# STM32H750-MotherBoard2.net
KiCad netlist of a schematic drawn in Altium Designer
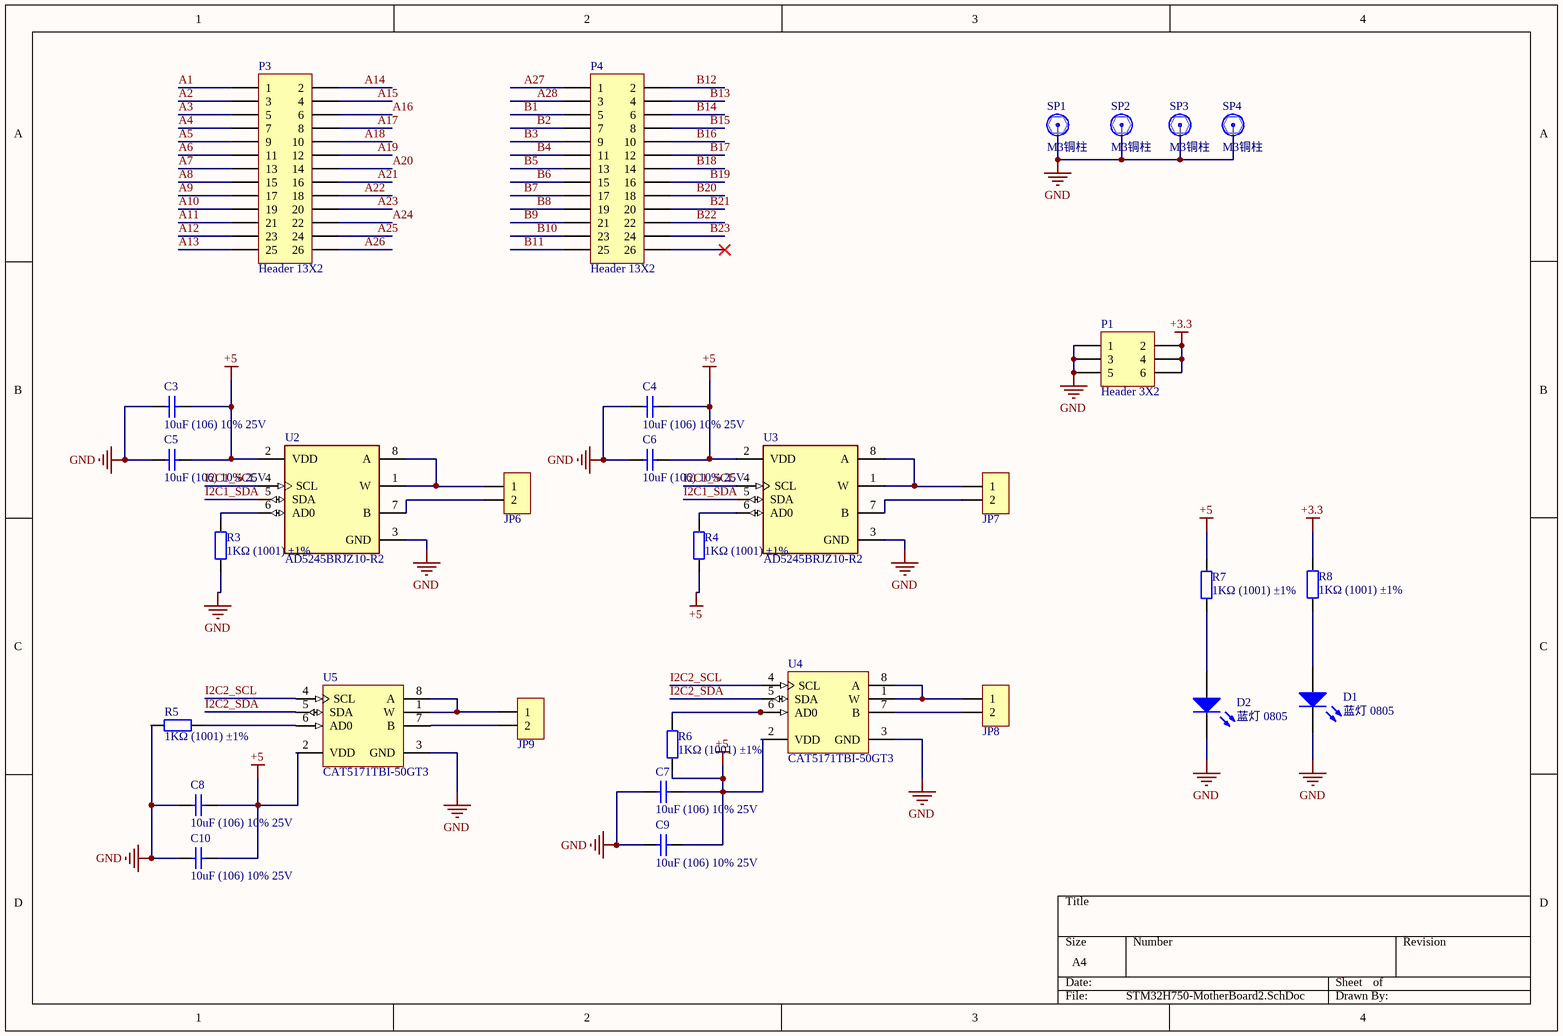
[diagram p0: STM32H750-MotherBoard2.SchDoc]

(export (version "E")
  (design (tool "Eeschema 10.0.6"))
  (components
    (comp (ref "C3")
      (value "10uF (106) 10% 25V")
      (footprint "0805_C")
      (description "贴片电容")
      (libsource (lib "JLC") (part "0805 10uF (106) 10% 25V"))
    )
    (comp (ref "C4")
      (value "10uF (106) 10% 25V")
      (footprint "0805_C")
      (description "贴片电容")
      (libsource (lib "JLC") (part "0805 10uF (106) 10% 25V"))
    )
    (comp (ref "C5")
      (value "10uF (106) 10% 25V")
      (footprint "0805_C")
      (description "贴片电容")
      (libsource (lib "JLC") (part "0805 10uF (106) 10% 25V"))
    )
    (comp (ref "C6")
      (value "10uF (106) 10% 25V")
      (footprint "0805_C")
      (description "贴片电容")
      (libsource (lib "JLC") (part "0805 10uF (106) 10% 25V"))
    )
    (comp (ref "C7")
      (value "10uF (106) 10% 25V")
      (footprint "0805_C")
      (description "贴片电容")
      (libsource (lib "JLC") (part "0805 10uF (106) 10% 25V"))
    )
    (comp (ref "C8")
      (value "10uF (106) 10% 25V")
      (footprint "0805_C")
      (description "贴片电容")
      (libsource (lib "JLC") (part "0805 10uF (106) 10% 25V"))
    )
    (comp (ref "C9")
      (value "10uF (106) 10% 25V")
      (footprint "0805_C")
      (description "贴片电容")
      (libsource (lib "JLC") (part "0805 10uF (106) 10% 25V"))
    )
    (comp (ref "C10")
      (value "10uF (106) 10% 25V")
      (footprint "0805_C")
      (description "贴片电容")
      (libsource (lib "JLC") (part "0805 10uF (106) 10% 25V"))
    )
    (comp (ref "D1")
      (value "蓝灯 0805")
      (footprint "0805_LED_S1")
      (description "发光二极管")
      (libsource (lib "JLC") (part "0805 蓝灯"))
    )
    (comp (ref "D2")
      (value "蓝灯 0805")
      (footprint "0805_LED_S1")
      (description "发光二极管")
      (libsource (lib "JLC") (part "0805 蓝灯"))
    )
    (comp (ref "JP6")
      (value "HDR-1X2")
      (footprint "XH2.54-LI-2P")
      (description "2P接插件")
      (libsource (lib "XH2.54") (part "Header 2"))
    )
    (comp (ref "JP7")
      (value "HDR-1X2")
      (footprint "XH2.54-LI-2P")
      (description "2P接插件")
      (libsource (lib "XH2.54") (part "Header 2"))
    )
    (comp (ref "JP8")
      (value "HDR-1X2")
      (footprint "XH2.54-LI-2P")
      (description "2P接插件")
      (libsource (lib "XH2.54") (part "Header 2"))
    )
    (comp (ref "JP9")
      (value "HDR-1X2")
      (footprint "XH2.54-LI-2P")
      (description "2P接插件")
      (libsource (lib "XH2.54") (part "Header 2"))
    )
    (comp (ref "P1")
      (value "Header 3X2")
      (footprint "HDR2X3")
      (description "Header, 3-Pin, Dual row")
      (fields (field (name "PUBLISHER") "Altium Limited"))
      (libsource (lib "Miscellaneous Connectors") (part "Header 3X2"))
    )
    (comp (ref "P3")
      (value "Header 13X2")
      (footprint "HDR2X13")
      (description "Header, 13-Pin, Dual row")
      (fields (field (name "PUBLISHER") "Altium Limited"))
      (libsource (lib "Miscellaneous Connectors") (part "Header 13X2"))
    )
    (comp (ref "P4")
      (value "Header 13X2")
      (footprint "HDR2X13")
      (description "Header, 13-Pin, Dual row")
      (fields (field (name "PUBLISHER") "Altium Limited"))
      (libsource (lib "Miscellaneous Connectors") (part "Header 13X2"))
    )
    (comp (ref "R3")
      (value "1KΩ (1001) ±1%")
      (footprint "0805_R")
      (description "贴片电阻")
      (libsource (lib "JLC") (part "0805 1KΩ (1001) 1%"))
    )
    (comp (ref "R4")
      (value "1KΩ (1001) ±1%")
      (footprint "0805_R")
      (description "贴片电阻")
      (libsource (lib "JLC") (part "0805 1KΩ (1001) 1%"))
    )
    (comp (ref "R5")
      (value "1KΩ (1001) ±1%")
      (footprint "0805_R")
      (description "贴片电阻")
      (libsource (lib "") (part "0805 1KΩ (1001) 1%_1"))
    )
    (comp (ref "R6")
      (value "1KΩ (1001) ±1%")
      (footprint "0805_R")
      (description "贴片电阻")
      (libsource (lib "JLC") (part "0805 1KΩ (1001) 1%"))
    )
    (comp (ref "R7")
      (value "1KΩ (1001) ±1%")
      (footprint "0805_R")
      (description "贴片电阻")
      (libsource (lib "JLC") (part "0805 1KΩ (1001) 1%"))
    )
    (comp (ref "R8")
      (value "1KΩ (1001) ±1%")
      (footprint "0805_R")
      (description "贴片电阻")
      (libsource (lib "JLC") (part "0805 1KΩ (1001) 1%"))
    )
    (comp (ref "SP1")
      (value "M3铜柱")
      (footprint "M3x4_L")
      (description "铜柱")
      (libsource (lib "铜柱-测试点-电池座-蜂鸣器") (part "铜柱小焊盘"))
    )
    (comp (ref "SP2")
      (value "M3铜柱")
      (footprint "M3x4_L")
      (description "铜柱")
      (libsource (lib "铜柱-测试点-电池座-蜂鸣器") (part "铜柱小焊盘"))
    )
    (comp (ref "SP3")
      (value "M3铜柱")
      (footprint "M3x4_L")
      (description "铜柱")
      (libsource (lib "铜柱-测试点-电池座-蜂鸣器") (part "铜柱小焊盘"))
    )
    (comp (ref "SP4")
      (value "M3铜柱")
      (footprint "M3x4_L")
      (description "铜柱")
      (libsource (lib "铜柱-测试点-电池座-蜂鸣器") (part "铜柱小焊盘"))
    )
    (comp (ref "U2")
      (value "AD5245BRJZ10-R2")
      (footprint "FP-RJ-8-IPC_C")
      (description "IC DGT POT 10KOHM 256TAP SOT23-8")
      (fields (field (name "TOLERANCE") "30%") (field (name "MANUFACTURER") "Analog Devices"))
      (libsource (lib "Altium Content Vault") (part "8d408c839f24318d0976f3536df8182"))
    )
    (comp (ref "U3")
      (value "AD5245BRJZ10-R2")
      (footprint "FP-RJ-8-IPC_C")
      (description "IC DGT POT 10KOHM 256TAP SOT23-8")
      (fields (field (name "TOLERANCE") "30%") (field (name "MANUFACTURER") "Analog Devices"))
      (libsource (lib "Altium Content Vault") (part "8d408c839f24318d0976f3536df8182"))
    )
    (comp (ref "U4")
      (value "CAT5171TBI-50GT3")
      (footprint "ONSC-SOT23-8-527AK-01_N")
      (fields (field (name "MANUFACTURER") "On Semiconductor"))
      (libsource (lib "Altium Content Vault") (part "ONSC-CAT5171-SOT23-8-527AK-01"))
    )
    (comp (ref "U5")
      (value "CAT5171TBI-50GT3")
      (footprint "ONSC-SOT23-8-527AK-01_N")
      (fields (field (name "MANUFACTURER") "On Semiconductor"))
      (libsource (lib "Altium Content Vault") (part "ONSC-CAT5171-SOT23-8-527AK-01"))
    )
  )
  (nets
    (net (code "1") (name "+3.3") (class "Default")
      (node (ref "P1") (pin "2") (pinfunction "2_2") (pintype "passive"))
      (node (ref "P1") (pin "4") (pinfunction "4_4") (pintype "passive"))
      (node (ref "P1") (pin "6") (pinfunction "6_6") (pintype "passive"))
      (node (ref "R8") (pin "2") (pinfunction "2_2") (pintype "passive"))
    )
    (net (code "2") (name "+5") (class "Default")
      (node (ref "C10") (pin "2") (pinfunction "2_2") (pintype "passive"))
      (node (ref "C3") (pin "2") (pinfunction "2_2") (pintype "passive"))
      (node (ref "C4") (pin "2") (pinfunction "2_2") (pintype "passive"))
      (node (ref "C5") (pin "2") (pinfunction "2_2") (pintype "passive"))
      (node (ref "C6") (pin "2") (pinfunction "2_2") (pintype "passive"))
      (node (ref "C7") (pin "2") (pinfunction "2_2") (pintype "passive"))
      (node (ref "C8") (pin "2") (pinfunction "2_2") (pintype "passive"))
      (node (ref "C9") (pin "2") (pinfunction "2_2") (pintype "passive"))
      (node (ref "R4") (pin "1") (pinfunction "1_1") (pintype "passive"))
      (node (ref "R6") (pin "1") (pinfunction "1_1") (pintype "passive"))
      (node (ref "R7") (pin "2") (pinfunction "2_2") (pintype "passive"))
      (node (ref "U2") (pin "2") (pinfunction "VDD_2") (pintype "power_in"))
      (node (ref "U3") (pin "2") (pinfunction "VDD_2") (pintype "power_in"))
      (node (ref "U4") (pin "2") (pinfunction "VDD_2") (pintype "power_in"))
      (node (ref "U5") (pin "2") (pinfunction "VDD_2") (pintype "power_in"))
    )
    (net (code "3") (name "/A1") (class "Default")
      (node (ref "P3") (pin "1") (pinfunction "1_1") (pintype "passive"))
    )
    (net (code "4") (name "/A2") (class "Default")
      (node (ref "P3") (pin "3") (pinfunction "3_3") (pintype "passive"))
    )
    (net (code "5") (name "/A3") (class "Default")
      (node (ref "P3") (pin "5") (pinfunction "5_5") (pintype "passive"))
    )
    (net (code "6") (name "/A4") (class "Default")
      (node (ref "P3") (pin "7") (pinfunction "7_7") (pintype "passive"))
    )
    (net (code "7") (name "/A5") (class "Default")
      (node (ref "P3") (pin "9") (pinfunction "9_9") (pintype "passive"))
    )
    (net (code "8") (name "/A6") (class "Default")
      (node (ref "P3") (pin "11") (pinfunction "11_11") (pintype "passive"))
    )
    (net (code "9") (name "/A7") (class "Default")
      (node (ref "P3") (pin "13") (pinfunction "13_13") (pintype "passive"))
    )
    (net (code "10") (name "/A8") (class "Default")
      (node (ref "P3") (pin "15") (pinfunction "15_15") (pintype "passive"))
    )
    (net (code "11") (name "/A9") (class "Default")
      (node (ref "P3") (pin "17") (pinfunction "17_17") (pintype "passive"))
    )
    (net (code "12") (name "/A10") (class "Default")
      (node (ref "P3") (pin "19") (pinfunction "19_19") (pintype "passive"))
    )
    (net (code "13") (name "/A11") (class "Default")
      (node (ref "P3") (pin "21") (pinfunction "21_21") (pintype "passive"))
    )
    (net (code "14") (name "/A12") (class "Default")
      (node (ref "P3") (pin "23") (pinfunction "23_23") (pintype "passive"))
    )
    (net (code "15") (name "/A13") (class "Default")
      (node (ref "P3") (pin "25") (pinfunction "25_25") (pintype "passive"))
    )
    (net (code "16") (name "/A14") (class "Default")
      (node (ref "P3") (pin "2") (pinfunction "2_2") (pintype "passive"))
    )
    (net (code "17") (name "/A15") (class "Default")
      (node (ref "P3") (pin "4") (pinfunction "4_4") (pintype "passive"))
    )
    (net (code "18") (name "/A16") (class "Default")
      (node (ref "P3") (pin "6") (pinfunction "6_6") (pintype "passive"))
    )
    (net (code "19") (name "/A17") (class "Default")
      (node (ref "P3") (pin "8") (pinfunction "8_8") (pintype "passive"))
    )
    (net (code "20") (name "/A18") (class "Default")
      (node (ref "P3") (pin "10") (pinfunction "10_10") (pintype "passive"))
    )
    (net (code "21") (name "/A19") (class "Default")
      (node (ref "P3") (pin "12") (pinfunction "12_12") (pintype "passive"))
    )
    (net (code "22") (name "/A20") (class "Default")
      (node (ref "P3") (pin "14") (pinfunction "14_14") (pintype "passive"))
    )
    (net (code "23") (name "/A21") (class "Default")
      (node (ref "P3") (pin "16") (pinfunction "16_16") (pintype "passive"))
    )
    (net (code "24") (name "/A22") (class "Default")
      (node (ref "P3") (pin "18") (pinfunction "18_18") (pintype "passive"))
    )
    (net (code "25") (name "/A23") (class "Default")
      (node (ref "P3") (pin "20") (pinfunction "20_20") (pintype "passive"))
    )
    (net (code "26") (name "/A24") (class "Default")
      (node (ref "P3") (pin "22") (pinfunction "22_22") (pintype "passive"))
    )
    (net (code "27") (name "/A25") (class "Default")
      (node (ref "P3") (pin "24") (pinfunction "24_24") (pintype "passive"))
    )
    (net (code "28") (name "/A26") (class "Default")
      (node (ref "P3") (pin "26") (pinfunction "26_26") (pintype "passive"))
    )
    (net (code "29") (name "/A27") (class "Default")
      (node (ref "P4") (pin "1") (pinfunction "1_1") (pintype "passive"))
    )
    (net (code "30") (name "/A28") (class "Default")
      (node (ref "P4") (pin "3") (pinfunction "3_3") (pintype "passive"))
    )
    (net (code "31") (name "/B1") (class "Default")
      (node (ref "P4") (pin "5") (pinfunction "5_5") (pintype "passive"))
    )
    (net (code "32") (name "/B2") (class "Default")
      (node (ref "P4") (pin "7") (pinfunction "7_7") (pintype "passive"))
    )
    (net (code "33") (name "/B3") (class "Default")
      (node (ref "P4") (pin "9") (pinfunction "9_9") (pintype "passive"))
    )
    (net (code "34") (name "/B4") (class "Default")
      (node (ref "P4") (pin "11") (pinfunction "11_11") (pintype "passive"))
    )
    (net (code "35") (name "/B5") (class "Default")
      (node (ref "P4") (pin "13") (pinfunction "13_13") (pintype "passive"))
    )
    (net (code "36") (name "/B6") (class "Default")
      (node (ref "P4") (pin "15") (pinfunction "15_15") (pintype "passive"))
    )
    (net (code "37") (name "/B7") (class "Default")
      (node (ref "P4") (pin "17") (pinfunction "17_17") (pintype "passive"))
    )
    (net (code "38") (name "/B8") (class "Default")
      (node (ref "P4") (pin "19") (pinfunction "19_19") (pintype "passive"))
    )
    (net (code "39") (name "/B9") (class "Default")
      (node (ref "P4") (pin "21") (pinfunction "21_21") (pintype "passive"))
    )
    (net (code "40") (name "/B10") (class "Default")
      (node (ref "P4") (pin "23") (pinfunction "23_23") (pintype "passive"))
    )
    (net (code "41") (name "/B11") (class "Default")
      (node (ref "P4") (pin "25") (pinfunction "25_25") (pintype "passive"))
    )
    (net (code "42") (name "/B12") (class "Default")
      (node (ref "P4") (pin "2") (pinfunction "2_2") (pintype "passive"))
    )
    (net (code "43") (name "/B13") (class "Default")
      (node (ref "P4") (pin "4") (pinfunction "4_4") (pintype "passive"))
    )
    (net (code "44") (name "/B14") (class "Default")
      (node (ref "P4") (pin "6") (pinfunction "6_6") (pintype "passive"))
    )
    (net (code "45") (name "/B15") (class "Default")
      (node (ref "P4") (pin "8") (pinfunction "8_8") (pintype "passive"))
    )
    (net (code "46") (name "/B16") (class "Default")
      (node (ref "P4") (pin "10") (pinfunction "10_10") (pintype "passive"))
    )
    (net (code "47") (name "/B17") (class "Default")
      (node (ref "P4") (pin "12") (pinfunction "12_12") (pintype "passive"))
    )
    (net (code "48") (name "/B18") (class "Default")
      (node (ref "P4") (pin "14") (pinfunction "14_14") (pintype "passive"))
    )
    (net (code "49") (name "/B19") (class "Default")
      (node (ref "P4") (pin "16") (pinfunction "16_16") (pintype "passive"))
    )
    (net (code "50") (name "/B20") (class "Default")
      (node (ref "P4") (pin "18") (pinfunction "18_18") (pintype "passive"))
    )
    (net (code "51") (name "/B21") (class "Default")
      (node (ref "P4") (pin "20") (pinfunction "20_20") (pintype "passive"))
    )
    (net (code "52") (name "/B22") (class "Default")
      (node (ref "P4") (pin "22") (pinfunction "22_22") (pintype "passive"))
    )
    (net (code "53") (name "/B23") (class "Default")
      (node (ref "P4") (pin "24") (pinfunction "24_24") (pintype "passive"))
    )
    (net (code "54") (name "/I2C1_SCL") (class "Default")
      (node (ref "U2") (pin "4") (pinfunction "SCL_4") (pintype "input"))
      (node (ref "U3") (pin "4") (pinfunction "SCL_4") (pintype "input"))
    )
    (net (code "55") (name "/I2C1_SDA") (class "Default")
      (node (ref "U2") (pin "5") (pinfunction "SDA_5") (pintype "bidirectional"))
      (node (ref "U3") (pin "5") (pinfunction "SDA_5") (pintype "bidirectional"))
    )
    (net (code "56") (name "/I2C2_SCL") (class "Default")
      (node (ref "U4") (pin "4") (pinfunction "SCL_4") (pintype "input"))
      (node (ref "U5") (pin "4") (pinfunction "SCL_4") (pintype "input"))
    )
    (net (code "57") (name "/I2C2_SDA") (class "Default")
      (node (ref "U4") (pin "5") (pinfunction "SDA_5") (pintype "bidirectional"))
      (node (ref "U5") (pin "5") (pinfunction "SDA_5") (pintype "bidirectional"))
    )
    (net (code "58") (name "GND") (class "Default")
      (node (ref "C10") (pin "1") (pinfunction "1_1") (pintype "passive"))
      (node (ref "C3") (pin "1") (pinfunction "1_1") (pintype "passive"))
      (node (ref "C4") (pin "1") (pinfunction "1_1") (pintype "passive"))
      (node (ref "C5") (pin "1") (pinfunction "1_1") (pintype "passive"))
      (node (ref "C6") (pin "1") (pinfunction "1_1") (pintype "passive"))
      (node (ref "C7") (pin "1") (pinfunction "1_1") (pintype "passive"))
      (node (ref "C8") (pin "1") (pinfunction "1_1") (pintype "passive"))
      (node (ref "C9") (pin "1") (pinfunction "1_1") (pintype "passive"))
      (node (ref "D1") (pin "K") (pinfunction "K_K") (pintype "passive"))
      (node (ref "D2") (pin "K") (pinfunction "K_K") (pintype "passive"))
      (node (ref "P1") (pin "1") (pinfunction "1_1") (pintype "passive"))
      (node (ref "P1") (pin "3") (pinfunction "3_3") (pintype "passive"))
      (node (ref "P1") (pin "5") (pinfunction "5_5") (pintype "passive"))
      (node (ref "R3") (pin "1") (pinfunction "1_1") (pintype "passive"))
      (node (ref "R5") (pin "1") (pinfunction "1_1") (pintype "passive"))
      (node (ref "SP1") (pin "1") (pinfunction "1_1") (pintype "passive"))
      (node (ref "SP2") (pin "1") (pinfunction "1_1") (pintype "passive"))
      (node (ref "SP3") (pin "1") (pinfunction "1_1") (pintype "passive"))
      (node (ref "SP4") (pin "1") (pinfunction "1_1") (pintype "passive"))
      (node (ref "U2") (pin "3") (pinfunction "GND_3") (pintype "power_in"))
      (node (ref "U3") (pin "3") (pinfunction "GND_3") (pintype "power_in"))
      (node (ref "U4") (pin "3") (pinfunction "GND_3") (pintype "power_in"))
      (node (ref "U5") (pin "3") (pinfunction "GND_3") (pintype "power_in"))
    )
    (net (code "59") (name "Net-(D1-PadA)") (class "Default")
      (node (ref "D1") (pin "A") (pinfunction "A_A") (pintype "passive"))
      (node (ref "R8") (pin "1") (pinfunction "1_1") (pintype "passive"))
    )
    (net (code "60") (name "Net-(D2-PadA)") (class "Default")
      (node (ref "D2") (pin "A") (pinfunction "A_A") (pintype "passive"))
      (node (ref "R7") (pin "1") (pinfunction "1_1") (pintype "passive"))
    )
    (net (code "61") (name "Net-(U2-A)") (class "Default")
      (node (ref "JP6") (pin "1") (pinfunction "1_1") (pintype "passive"))
      (node (ref "U2") (pin "1") (pinfunction "W_1") (pintype "passive"))
      (node (ref "U2") (pin "8") (pinfunction "A_8") (pintype "passive"))
    )
    (net (code "62") (name "Net-(U2-AD0)") (class "Default")
      (node (ref "R3") (pin "2") (pinfunction "2_2") (pintype "passive"))
      (node (ref "U2") (pin "6") (pinfunction "AD0_6") (pintype "bidirectional"))
    )
    (net (code "63") (name "Net-(U2-B)") (class "Default")
      (node (ref "JP6") (pin "2") (pinfunction "2_2") (pintype "passive"))
      (node (ref "U2") (pin "7") (pinfunction "B_7") (pintype "passive"))
    )
    (net (code "64") (name "Net-(U3-A)") (class "Default")
      (node (ref "JP7") (pin "1") (pinfunction "1_1") (pintype "passive"))
      (node (ref "U3") (pin "1") (pinfunction "W_1") (pintype "passive"))
      (node (ref "U3") (pin "8") (pinfunction "A_8") (pintype "passive"))
    )
    (net (code "65") (name "Net-(U3-AD0)") (class "Default")
      (node (ref "R4") (pin "2") (pinfunction "2_2") (pintype "passive"))
      (node (ref "U3") (pin "6") (pinfunction "AD0_6") (pintype "bidirectional"))
    )
    (net (code "66") (name "Net-(U3-B)") (class "Default")
      (node (ref "JP7") (pin "2") (pinfunction "2_2") (pintype "passive"))
      (node (ref "U3") (pin "7") (pinfunction "B_7") (pintype "passive"))
    )
    (net (code "67") (name "Net-(U4-A)") (class "Default")
      (node (ref "JP8") (pin "1") (pinfunction "1_1") (pintype "passive"))
      (node (ref "U4") (pin "1") (pinfunction "W_1") (pintype "passive"))
      (node (ref "U4") (pin "8") (pinfunction "A_8") (pintype "passive"))
    )
    (net (code "68") (name "Net-(U4-AD0)") (class "Default")
      (node (ref "R6") (pin "2") (pinfunction "2_2") (pintype "passive"))
      (node (ref "U4") (pin "6") (pinfunction "AD0_6") (pintype "input"))
    )
    (net (code "69") (name "Net-(U4-B)") (class "Default")
      (node (ref "JP8") (pin "2") (pinfunction "2_2") (pintype "passive"))
      (node (ref "U4") (pin "7") (pinfunction "B_7") (pintype "passive"))
    )
    (net (code "70") (name "Net-(U5-A)") (class "Default")
      (node (ref "JP9") (pin "1") (pinfunction "1_1") (pintype "passive"))
      (node (ref "U5") (pin "1") (pinfunction "W_1") (pintype "passive"))
      (node (ref "U5") (pin "8") (pinfunction "A_8") (pintype "passive"))
    )
    (net (code "71") (name "Net-(U5-AD0)") (class "Default")
      (node (ref "R5") (pin "2") (pinfunction "2_2") (pintype "passive"))
      (node (ref "U5") (pin "6") (pinfunction "AD0_6") (pintype "input"))
    )
    (net (code "72") (name "Net-(U5-B)") (class "Default")
      (node (ref "JP9") (pin "2") (pinfunction "2_2") (pintype "passive"))
      (node (ref "U5") (pin "7") (pinfunction "B_7") (pintype "passive"))
    )
    (net (code "73") (name "unconnected-(P4-Pad26)") (class "Default")
      (node (ref "P4") (pin "26") (pinfunction "26_26") (pintype "passive+no_connect"))
    )
  )
)
